# laser_sensor.net
KiCad netlist of a schematic drawn in EAGLE
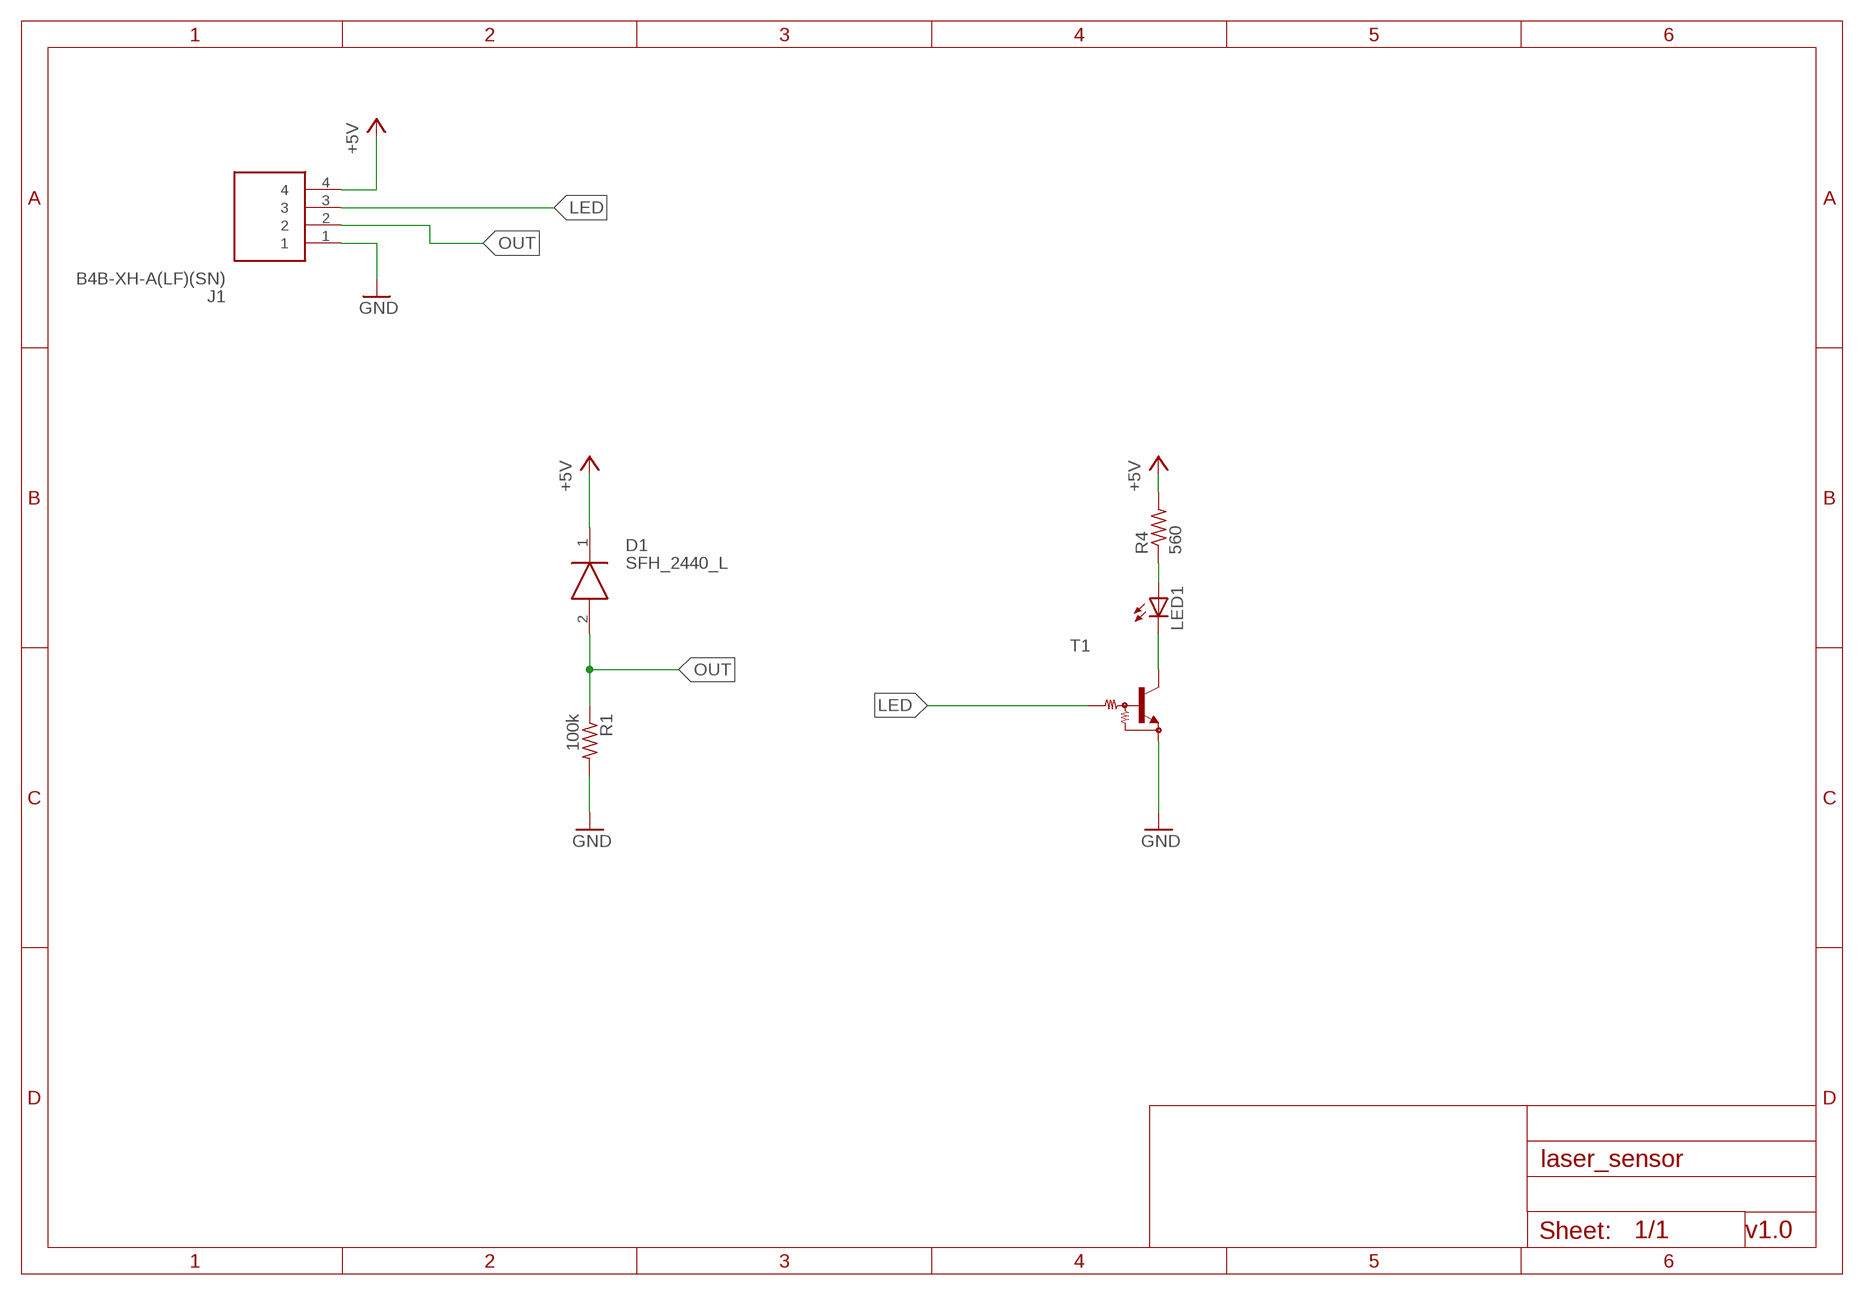
[diagram p0: schematic, sheet 1]

(export (version "E")
  (design (tool "Eeschema 10.0.6"))
  (components
    (comp (ref "D1")
      (value "SFH_2440_L")
      (footprint "eagle-import:SFH2440L")
      (fields
        (field (name "MANUFACTURER_PART_NUMBER") "SFH 2440 L")
        (field (name "MOUSER_PART_NUMBER") "720-SFH2440L")
        (field (name "RS_PART_NUMBER") "1243361P")
      )
      (libsource (lib "eagle-import") (part "SFH_2440_L"))
    )
    (comp (ref "J1")
      (value "B4B-XH-A(LF)(SN)")
      (footprint "eagle-import:SHDR4W64P0X250_1X4_1240X575X70")
      (fields (field (name "RS_PART_NUMBER") "1724913"))
      (libsource (lib "eagle-import") (part "B4B-XH-A(LF)(SN)"))
    )
    (comp (ref "LED1")
      (value "LED3MM")
      (footprint "eagle-import:LED3MM")
      (libsource (lib "eagle-import") (part "LED3MM"))
    )
    (comp (ref "R1")
      (value "100k")
      (footprint "eagle-import:R0603")
      (libsource (lib "eagle-import") (part "R-US_R0603"))
    )
    (comp (ref "R4")
      (value "560")
      (footprint "eagle-import:R0603")
      (libsource (lib "eagle-import") (part "R-US_R0603"))
    )
    (comp (ref "T1")
      (value "MUN2214T1-NPN_DRIVER-SC59-BEC")
      (footprint "eagle-import:SC59-BEC")
      (libsource (lib "eagle-import") (part "-NPN_DRIVER-SC59-BECMUN2214T1"))
    )
  )
  (nets
    (net (code "1") (name "+5V") (class "Default")
      (node (ref "D1") (pin "1") (pinfunction "ANODE_1") (pintype "bidirectional"))
      (node (ref "J1") (pin "4") (pinfunction "4_4") (pintype "bidirectional"))
      (node (ref "R4") (pin "2") (pinfunction "2_2") (pintype "passive"))
    )
    (net (code "2") (name "GND") (class "Default")
      (node (ref "J1") (pin "1") (pinfunction "1_1") (pintype "bidirectional"))
      (node (ref "R1") (pin "2") (pinfunction "2_2") (pintype "passive"))
      (node (ref "T1") (pin "E") (pinfunction "E_E") (pintype "passive"))
    )
    (net (code "3") (name "LED") (class "Default")
      (node (ref "J1") (pin "3") (pinfunction "3_3") (pintype "bidirectional"))
      (node (ref "T1") (pin "B") (pinfunction "B_B") (pintype "passive"))
    )
    (net (code "4") (name "Net-(LED1-C)") (class "Default")
      (node (ref "LED1") (pin "K") (pinfunction "C_K") (pintype "passive"))
      (node (ref "T1") (pin "C") (pinfunction "C_C") (pintype "passive"))
    )
    (net (code "5") (name "Net-(LED1-PadA)") (class "Default")
      (node (ref "LED1") (pin "A") (pinfunction "A_A") (pintype "passive"))
      (node (ref "R4") (pin "1") (pinfunction "1_1") (pintype "passive"))
    )
    (net (code "6") (name "OUT") (class "Default")
      (node (ref "D1") (pin "2") (pinfunction "CATHODE_2") (pintype "bidirectional"))
      (node (ref "J1") (pin "2") (pinfunction "2_2") (pintype "bidirectional"))
      (node (ref "R1") (pin "1") (pinfunction "1_1") (pintype "passive"))
    )
  )
)
